# 21_HUB.net
KiCad netlist of a schematic drawn in Altium Designer
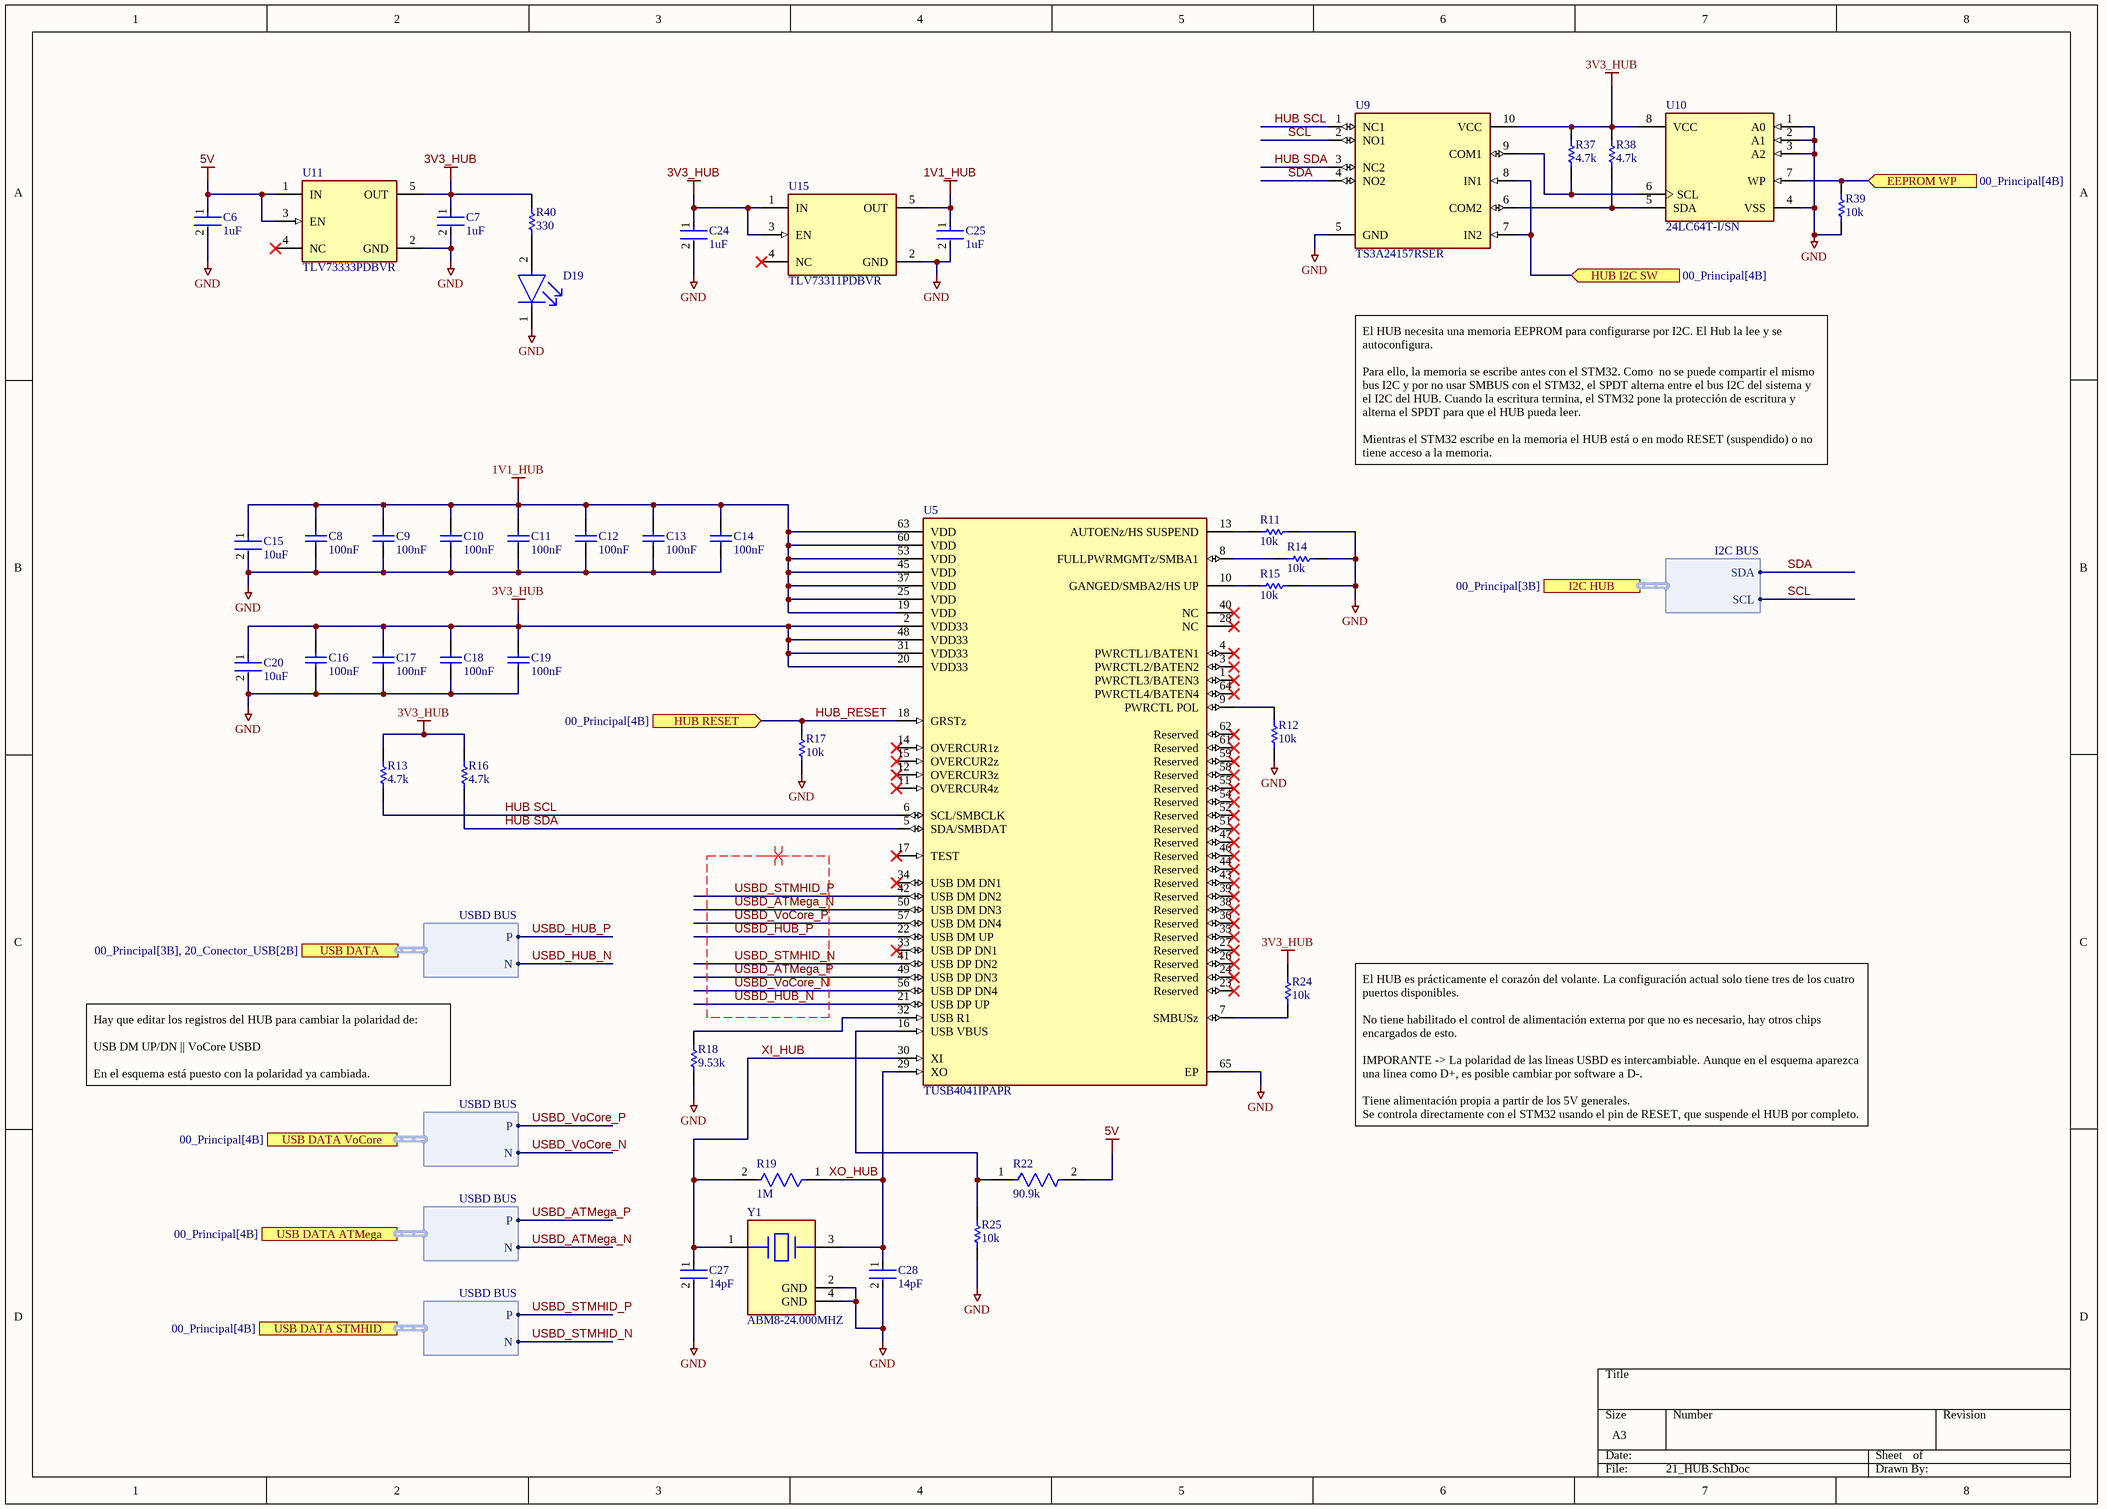
[diagram p0: 21_HUB.SchDoc]

(export (version "E")
  (design (tool "Eeschema 10.0.6"))
  (components
    (comp (ref "C6")
      (value "1uF")
      (footprint "FP-C0402C-BB-IPC_B")
      (description "CAP CER 1UF 16V X5R 0402")
      (fields (field (name "TOLERANCE") "10%"))
      (libsource (lib "Altium Content Vault") (part "b4654b650e69147ec39a6b967a45e02"))
    )
    (comp (ref "C7")
      (value "1uF")
      (footprint "FP-C0402C-BB-IPC_B")
      (description "CAP CER 1UF 16V X5R 0402")
      (fields (field (name "TOLERANCE") "10%"))
      (libsource (lib "Altium Content Vault") (part "b4654b650e69147ec39a6b967a45e02"))
    )
    (comp (ref "C8")
      (value "100nF")
      (footprint "CAPC1005X55X25NL05T05")
      (fields (field (name "MANUFACTURER") "Vitramon") (field (name "PART NUMBER") "VJ0402Y104KXJCW1BC"))
      (libsource (lib "Altium Content Vault") (part "CAP"))
    )
    (comp (ref "C9")
      (value "100nF")
      (footprint "CAPC1005X55X25NL05T05")
      (fields (field (name "MANUFACTURER") "Vitramon") (field (name "PART NUMBER") "VJ0402Y104KXJCW1BC"))
      (libsource (lib "Altium Content Vault") (part "CAP"))
    )
    (comp (ref "C10")
      (value "100nF")
      (footprint "CAPC1005X55X25NL05T05")
      (fields (field (name "MANUFACTURER") "Vitramon") (field (name "PART NUMBER") "VJ0402Y104KXJCW1BC"))
      (libsource (lib "Altium Content Vault") (part "CAP"))
    )
    (comp (ref "C11")
      (value "100nF")
      (footprint "CAPC1005X55X25NL05T05")
      (fields (field (name "MANUFACTURER") "Vitramon") (field (name "PART NUMBER") "VJ0402Y104KXJCW1BC"))
      (libsource (lib "Altium Content Vault") (part "CAP"))
    )
    (comp (ref "C12")
      (value "100nF")
      (footprint "CAPC1005X55X25NL05T05")
      (fields (field (name "MANUFACTURER") "Vitramon") (field (name "PART NUMBER") "VJ0402Y104KXJCW1BC"))
      (libsource (lib "Altium Content Vault") (part "CAP"))
    )
    (comp (ref "C13")
      (value "100nF")
      (footprint "CAPC1005X55X25NL05T05")
      (fields (field (name "MANUFACTURER") "Vitramon") (field (name "PART NUMBER") "VJ0402Y104KXJCW1BC"))
      (libsource (lib "Altium Content Vault") (part "CAP"))
    )
    (comp (ref "C14")
      (value "100nF")
      (footprint "CAPC1005X55X25NL05T05")
      (fields (field (name "MANUFACTURER") "Vitramon") (field (name "PART NUMBER") "VJ0402Y104KXJCW1BC"))
      (libsource (lib "Altium Content Vault") (part "CAP"))
    )
    (comp (ref "C15")
      (value "10uF")
      (footprint "FP-GRM155-0_2-MFG")
      (description "Chip Multilayer Ceramic Capacitors for General Purpose, 0402, 10uF, X5R, 15%, 20%, 4V")
      (libsource (lib "Altium Content Vault") (part "b4654b650e69147ec39a6b967a45e02"))
    )
    (comp (ref "C16")
      (value "100nF")
      (footprint "CAPC1005X55X25NL05T05")
      (fields (field (name "MANUFACTURER") "Vitramon") (field (name "PART NUMBER") "VJ0402Y104KXJCW1BC"))
      (libsource (lib "Altium Content Vault") (part "CAP"))
    )
    (comp (ref "C17")
      (value "100nF")
      (footprint "CAPC1005X55X25NL05T05")
      (fields (field (name "MANUFACTURER") "Vitramon") (field (name "PART NUMBER") "VJ0402Y104KXJCW1BC"))
      (libsource (lib "Altium Content Vault") (part "CAP"))
    )
    (comp (ref "C18")
      (value "100nF")
      (footprint "CAPC1005X55X25NL05T05")
      (fields (field (name "MANUFACTURER") "Vitramon") (field (name "PART NUMBER") "VJ0402Y104KXJCW1BC"))
      (libsource (lib "Altium Content Vault") (part "CAP"))
    )
    (comp (ref "C19")
      (value "100nF")
      (footprint "CAPC1005X55X25NL05T05")
      (fields (field (name "MANUFACTURER") "Vitramon") (field (name "PART NUMBER") "VJ0402Y104KXJCW1BC"))
      (libsource (lib "Altium Content Vault") (part "CAP"))
    )
    (comp (ref "C20")
      (value "10uF")
      (footprint "FP-GRM155-0_2-MFG")
      (description "Chip Multilayer Ceramic Capacitors for General Purpose, 0402, 10uF, X5R, 15%, 20%, 4V")
      (libsource (lib "Altium Content Vault") (part "b4654b650e69147ec39a6b967a45e02"))
    )
    (comp (ref "C24")
      (value "1uF")
      (footprint "FP-C0402C-BB-IPC_B")
      (description "CAP CER 1UF 16V X5R 0402")
      (fields (field (name "TOLERANCE") "10%"))
      (libsource (lib "Altium Content Vault") (part "b4654b650e69147ec39a6b967a45e02"))
    )
    (comp (ref "C25")
      (value "1uF")
      (footprint "FP-C0402C-BB-IPC_B")
      (description "CAP CER 1UF 16V X5R 0402")
      (fields (field (name "TOLERANCE") "10%"))
      (libsource (lib "Altium Content Vault") (part "b4654b650e69147ec39a6b967a45e02"))
    )
    (comp (ref "C27")
      (value "14pF")
      (footprint "FP-GJM155-0_05-IPC_C")
      (description "Multi-Layer Ceramic Capacitor 14pF C0G  ±1% 0402 Paper T/R")
      (libsource (lib "Altium Content Vault") (part "02cd4be3c70576c341d710602a673aa"))
    )
    (comp (ref "C28")
      (value "14pF")
      (footprint "FP-GJM155-0_05-IPC_C")
      (description "Multi-Layer Ceramic Capacitor 14pF C0G  ±1% 0402 Paper T/R")
      (libsource (lib "Altium Content Vault") (part "02cd4be3c70576c341d710602a673aa"))
    )
    (comp (ref "D19")
      (value "APHD1608LZGCK")
      (footprint "FP-APHD1608LZGCK-MFG")
      (description "LED GREEN CLEAR 1608 SMD")
      (libsource (lib "Altium Content Vault") (part "8706943c75ba83719d021d2fdc84c58"))
    )
    (comp (ref "R11")
      (value "10k")
      (footprint "RESC1005X40X25ML05T05")
      (fields (field (name "MANUFACTURER") "Panasonic") (field (name "PART NUMBER") "ERJ-2RHD1002X"))
      (libsource (lib "Altium Content Vault") (part "RES"))
    )
    (comp (ref "R12")
      (value "10k")
      (footprint "RESC1005X40X25NL05T05")
      (fields (field (name "MANUFACTURER") "Panasonic") (field (name "PART NUMBER") "ERJ-2RHD1002X"))
      (libsource (lib "Altium Content Vault") (part "RES"))
    )
    (comp (ref "R13")
      (value "4.7k")
      (footprint "RESC1005X40X25ML05T10")
      (fields (field (name "MANUFACTURER") "Panasonic") (field (name "PART NUMBER") "ERJ-S02F4701X"))
      (libsource (lib "Altium Content Vault") (part "RES"))
    )
    (comp (ref "R14")
      (value "10k")
      (footprint "RESC1005X40X25ML05T05")
      (fields (field (name "MANUFACTURER") "Panasonic") (field (name "PART NUMBER") "ERJ-2RHD1002X"))
      (libsource (lib "Altium Content Vault") (part "RES"))
    )
    (comp (ref "R15")
      (value "10k")
      (footprint "RESC1005X40X25ML05T05")
      (fields (field (name "MANUFACTURER") "Panasonic") (field (name "PART NUMBER") "ERJ-2RHD1002X"))
      (libsource (lib "Altium Content Vault") (part "RES"))
    )
    (comp (ref "R16")
      (value "4.7k")
      (footprint "RESC1005X40X25ML05T10")
      (fields (field (name "MANUFACTURER") "Panasonic") (field (name "PART NUMBER") "ERJ-S02F4701X"))
      (libsource (lib "Altium Content Vault") (part "RES"))
    )
    (comp (ref "R17")
      (value "10k")
      (footprint "RESC1005X40X25ML05T05")
      (fields (field (name "MANUFACTURER") "Panasonic") (field (name "PART NUMBER") "ERJ-2RHD1002X"))
      (libsource (lib "Altium Content Vault") (part "RES"))
    )
    (comp (ref "R18")
      (value "9.53k")
      (footprint "RESC1609X50X30NL10T20")
      (fields (field (name "MANUFACTURER") "Vishay Dale") (field (name "PART NUMBER") "CRCW06039K53FKEA"))
      (libsource (lib "Altium Content Vault") (part "RES"))
    )
    (comp (ref "R19")
      (value "1M")
      (footprint "FP-CRCW0402-C-e3-IPC_B")
      (description "RES 1M OHM 1% 1/16W 0402")
      (fields (field (name "TOLERANCE") "1%"))
      (libsource (lib "Altium Content Vault") (part "1029c3af85768c4190bb7ad29bc67b5"))
    )
    (comp (ref "R22")
      (value "90.9k")
      (footprint "FP-RK73H1E-IPC_C")
      (description "90.9kΩ ±1% 0.1W Chip Resistor 0402 Flat Chip (Anti-Sulfuration) AEC-Q200 Qualified")
      (fields (field (name "TOLERANCE") "1%"))
      (libsource (lib "Altium Content Vault") (part "1029c3af85768c4190bb7ad29bc67b5"))
    )
    (comp (ref "R24")
      (value "10k")
      (footprint "RESC1005X40X25NL05T05")
      (fields (field (name "MANUFACTURER") "Panasonic") (field (name "PART NUMBER") "ERJ-2RHD1002X"))
      (libsource (lib "Altium Content Vault") (part "RES"))
    )
    (comp (ref "R25")
      (value "10k")
      (footprint "RESC1005X40X25NL05T05")
      (fields (field (name "MANUFACTURER") "Panasonic") (field (name "PART NUMBER") "ERJ-2RHD1002X"))
      (libsource (lib "Altium Content Vault") (part "RES"))
    )
    (comp (ref "R37")
      (value "4.7k")
      (footprint "RESC1005X40X25ML05T10")
      (fields (field (name "MANUFACTURER") "Panasonic") (field (name "PART NUMBER") "ERJ-S02F4701X"))
      (libsource (lib "Altium Content Vault") (part "RES"))
    )
    (comp (ref "R38")
      (value "4.7k")
      (footprint "RESC1005X40X25ML05T10")
      (fields (field (name "MANUFACTURER") "Panasonic") (field (name "PART NUMBER") "ERJ-S02F4701X"))
      (libsource (lib "Altium Content Vault") (part "RES"))
    )
    (comp (ref "R39")
      (value "10k")
      (footprint "RESC1005X40X25ML05T05")
      (fields (field (name "MANUFACTURER") "Panasonic") (field (name "PART NUMBER") "ERJ-2RHD1002X"))
      (libsource (lib "Altium Content Vault") (part "RES"))
    )
    (comp (ref "R40")
      (value "330")
      (footprint "RESC1005X40X25NL10T10")
      (fields (field (name "MANUFACTURER") "Panasonic") (field (name "PART NUMBER") "ERA2AEB331X"))
      (libsource (lib "Altium Content Vault") (part "RES"))
    )
    (comp (ref "U5")
      (value "TUSB4041IPAPR")
      (footprint "FP-PAP0064K-MFG")
      (description "IC USB 2.0 4PORT HUB 64HTQFP")
      (fields
        (field (name "MANUFACTURER") "Texas Instruments")
        (field (name "OCTOPART") "https://octopart.com/tusb4041ipapr-texas+instruments-61734371")
      )
      (libsource (lib "Altium Content Vault") (part "5e978d452e673cf9c6e58b86f9ac1bd"))
    )
    (comp (ref "U9")
      (value "TS3A24157RSER")
      (footprint "FP-RSE0010A-MFG")
      (description "IC SWITCH DUAL SPDT 10UQFN")
      (libsource (lib "Altium Content Vault") (part "1cf126cdf601fc2f4e01c6c6da6e1d2"))
    )
    (comp (ref "U10")
      (value "24LC64T-I/SN")
      (footprint "FP-C04-057-SN-MFG")
      (description "IC EEPROM 64K I2C 400KHZ 8SOIC")
      (fields
        (field (name "OCTOPART") "https://octopart.com/24lc64t-i%2Fsn-microchip-451854")
        (field (name "MANUFACTURER") "Microchip Technology")
      )
      (libsource (lib "Altium Content Vault") (part "aa9a952ee66a023cd78eade27961581"))
    )
    (comp (ref "U11")
      (value "TLV73333PDBVR")
      (footprint "FP-DBV0005A-MFG")
      (description "IC REG LINEAR 3.3V 300MA SOT23-5")
      (fields
        (field (name "MANUFACTURER") "Texas Instruments")
        (field (name "OCTOPART") "https://octopart.com/tlv73333pdbvr-texas+instruments-51080890")
      )
      (libsource (lib "Altium Content Vault") (part "10cdd6a861ce8db355dac0efc8b397e"))
    )
    (comp (ref "U15")
      (value "TLV73311PDBVR")
      (footprint "FP-DBV0005A-IPC_C")
      (description "IC REG LINEAR 1.1V 300MA SOT23-5")
      (libsource (lib "Altium Content Vault") (part "66ca6db733a9cb813c480efc7723418"))
    )
    (comp (ref "Y1")
      (value "ABM8-24.000MHZ")
      (footprint "FP-ABM8-MFG")
      (description "Crystal 24MHz ±10ppm 12pF SMD-4 3.2mm x 2.5mm")
      (libsource (lib "Altium Content Vault") (part "dfdb7f9a12507849fb681da9a70121c"))
    )
  )
  (nets
    (net (code "4") (name "/EEPROM WP") (class "Default")
      (node (ref "R39") (pin "1") (pinfunction "1_1") (pintype "passive"))
      (node (ref "U10") (pin "7") (pinfunction "WP_7") (pintype "input"))
    )
    (net (code "5") (name "/HUB I2C SW") (class "Default")
      (node (ref "U9") (pin "7") (pinfunction "IN2_7") (pintype "input"))
      (node (ref "U9") (pin "8") (pinfunction "IN1_8") (pintype "input"))
    )
    (net (code "6") (name "/HUB SCL") (class "Default")
      (node (ref "R13") (pin "1") (pinfunction "1_1") (pintype "passive"))
      (node (ref "U5") (pin "6") (pinfunction "SCL/SMBCLK_6") (pintype "bidirectional"))
      (node (ref "U9") (pin "1") (pinfunction "NC1_1") (pintype "bidirectional"))
    )
    (net (code "7") (name "/HUB SDA") (class "Default")
      (node (ref "R16") (pin "1") (pinfunction "1_1") (pintype "passive"))
      (node (ref "U5") (pin "5") (pinfunction "SDA/SMBDAT_5") (pintype "bidirectional"))
      (node (ref "U9") (pin "3") (pinfunction "NC2_3") (pintype "bidirectional"))
    )
    (net (code "8") (name "/HUB_RESET") (class "Default")
      (node (ref "R17") (pin "1") (pinfunction "1_1") (pintype "passive"))
      (node (ref "U5") (pin "18") (pinfunction "GRSTz_18") (pintype "input"))
    )
    (net (code "9") (name "/SCL") (class "Default")
      (node (ref "U9") (pin "2") (pinfunction "NO1_2") (pintype "bidirectional"))
    )
    (net (code "10") (name "/SDA") (class "Default")
      (node (ref "U9") (pin "4") (pinfunction "NO2_4") (pintype "bidirectional"))
    )
    (net (code "11") (name "/USBD_ATMega_N") (class "Default")
      (node (ref "U5") (pin "50") (pinfunction "USB_DM_DN3_50") (pintype "bidirectional"))
    )
    (net (code "12") (name "/USBD_ATMega_P") (class "Default")
      (node (ref "U5") (pin "49") (pinfunction "USB_DP_DN3_49") (pintype "bidirectional"))
    )
    (net (code "13") (name "/USBD_HUB_N") (class "Default")
      (node (ref "U5") (pin "21") (pinfunction "USB_DP_UP_21") (pintype "bidirectional"))
    )
    (net (code "14") (name "/USBD_HUB_P") (class "Default")
      (node (ref "U5") (pin "22") (pinfunction "USB_DM_UP_22") (pintype "bidirectional"))
    )
    (net (code "15") (name "/USBD_STMHID_N") (class "Default")
      (node (ref "U5") (pin "41") (pinfunction "USB_DP_DN2_41") (pintype "bidirectional"))
    )
    (net (code "16") (name "/USBD_STMHID_P") (class "Default")
      (node (ref "U5") (pin "42") (pinfunction "USB_DM_DN2_42") (pintype "bidirectional"))
    )
    (net (code "17") (name "/USBD_VoCore_N") (class "Default")
      (node (ref "U5") (pin "56") (pinfunction "USB_DP_DN4_56") (pintype "bidirectional"))
    )
    (net (code "18") (name "/USBD_VoCore_P") (class "Default")
      (node (ref "U5") (pin "57") (pinfunction "USB_DM_DN4_57") (pintype "bidirectional"))
    )
    (net (code "19") (name "/XI_HUB") (class "Default")
      (node (ref "C27") (pin "1") (pinfunction "1_1") (pintype "passive"))
      (node (ref "R19") (pin "2") (pinfunction "2_2") (pintype "passive"))
      (node (ref "U5") (pin "30") (pinfunction "XI_30") (pintype "input"))
      (node (ref "Y1") (pin "1") (pinfunction "1_1") (pintype "passive"))
    )
    (net (code "20") (name "/XO_HUB") (class "Default")
      (node (ref "C28") (pin "1") (pinfunction "1_1") (pintype "passive"))
      (node (ref "R19") (pin "1") (pinfunction "1_1") (pintype "passive"))
      (node (ref "U5") (pin "29") (pinfunction "XO_29") (pintype "input"))
      (node (ref "Y1") (pin "3") (pinfunction "3_3") (pintype "passive"))
    )
    (net (code "23") (name "1V1_HUB") (class "Default")
      (node (ref "C10") (pin "2") (pinfunction "2_2") (pintype "passive"))
      (node (ref "C11") (pin "2") (pinfunction "2_2") (pintype "passive"))
      (node (ref "C12") (pin "2") (pinfunction "2_2") (pintype "passive"))
      (node (ref "C13") (pin "2") (pinfunction "2_2") (pintype "passive"))
      (node (ref "C14") (pin "2") (pinfunction "2_2") (pintype "passive"))
      (node (ref "C15") (pin "1") (pinfunction "1_1") (pintype "passive"))
      (node (ref "C25") (pin "1") (pinfunction "1_1") (pintype "passive"))
      (node (ref "C8") (pin "2") (pinfunction "2_2") (pintype "passive"))
      (node (ref "C9") (pin "2") (pinfunction "2_2") (pintype "passive"))
      (node (ref "U15") (pin "5") (pinfunction "OUT_5") (pintype "power_in"))
      (node (ref "U5") (pin "19") (pinfunction "VDD_19") (pintype "power_in"))
      (node (ref "U5") (pin "25") (pinfunction "VDD_25") (pintype "power_in"))
      (node (ref "U5") (pin "37") (pinfunction "VDD_37") (pintype "power_in"))
      (node (ref "U5") (pin "45") (pinfunction "VDD_45") (pintype "power_in"))
      (node (ref "U5") (pin "53") (pinfunction "VDD_53") (pintype "power_in"))
      (node (ref "U5") (pin "60") (pinfunction "VDD_60") (pintype "power_in"))
      (node (ref "U5") (pin "63") (pinfunction "VDD_63") (pintype "power_in"))
    )
    (net (code "24") (name "3V3_HUB") (class "Default")
      (node (ref "C16") (pin "2") (pinfunction "2_2") (pintype "passive"))
      (node (ref "C17") (pin "2") (pinfunction "2_2") (pintype "passive"))
      (node (ref "C18") (pin "2") (pinfunction "2_2") (pintype "passive"))
      (node (ref "C19") (pin "2") (pinfunction "2_2") (pintype "passive"))
      (node (ref "C20") (pin "1") (pinfunction "1_1") (pintype "passive"))
      (node (ref "C24") (pin "1") (pinfunction "1_1") (pintype "passive"))
      (node (ref "C7") (pin "1") (pinfunction "1_1") (pintype "passive"))
      (node (ref "R13") (pin "2") (pinfunction "2_2") (pintype "passive"))
      (node (ref "R16") (pin "2") (pinfunction "2_2") (pintype "passive"))
      (node (ref "R24") (pin "2") (pinfunction "2_2") (pintype "passive"))
      (node (ref "R37") (pin "2") (pinfunction "2_2") (pintype "passive"))
      (node (ref "R38") (pin "2") (pinfunction "2_2") (pintype "passive"))
      (node (ref "R40") (pin "2") (pinfunction "2_2") (pintype "passive"))
      (node (ref "U10") (pin "8") (pinfunction "VCC_8") (pintype "power_in"))
      (node (ref "U11") (pin "5") (pinfunction "OUT_5") (pintype "power_in"))
      (node (ref "U15") (pin "1") (pinfunction "IN_1") (pintype "power_in"))
      (node (ref "U15") (pin "3") (pinfunction "EN_3") (pintype "input"))
      (node (ref "U5") (pin "2") (pinfunction "VDD33_2") (pintype "power_in"))
      (node (ref "U5") (pin "20") (pinfunction "VDD33_20") (pintype "power_in"))
      (node (ref "U5") (pin "31") (pinfunction "VDD33_31") (pintype "power_in"))
      (node (ref "U5") (pin "48") (pinfunction "VDD33_48") (pintype "power_in"))
      (node (ref "U9") (pin "10") (pinfunction "VCC_10") (pintype "power_in"))
    )
    (net (code "25") (name "5V") (class "Default")
      (node (ref "C6") (pin "1") (pinfunction "1_1") (pintype "passive"))
      (node (ref "R22") (pin "2") (pinfunction "2_2") (pintype "passive"))
      (node (ref "U11") (pin "1") (pinfunction "IN_1") (pintype "passive"))
      (node (ref "U11") (pin "3") (pinfunction "EN_3") (pintype "input"))
    )
    (net (code "26") (name "GND") (class "Default")
      (node (ref "C10") (pin "1") (pinfunction "1_1") (pintype "passive"))
      (node (ref "C11") (pin "1") (pinfunction "1_1") (pintype "passive"))
      (node (ref "C12") (pin "1") (pinfunction "1_1") (pintype "passive"))
      (node (ref "C13") (pin "1") (pinfunction "1_1") (pintype "passive"))
      (node (ref "C14") (pin "1") (pinfunction "1_1") (pintype "passive"))
      (node (ref "C15") (pin "2") (pinfunction "2_2") (pintype "passive"))
      (node (ref "C16") (pin "1") (pinfunction "1_1") (pintype "passive"))
      (node (ref "C17") (pin "1") (pinfunction "1_1") (pintype "passive"))
      (node (ref "C18") (pin "1") (pinfunction "1_1") (pintype "passive"))
      (node (ref "C19") (pin "1") (pinfunction "1_1") (pintype "passive"))
      (node (ref "C20") (pin "2") (pinfunction "2_2") (pintype "passive"))
      (node (ref "C24") (pin "2") (pinfunction "2_2") (pintype "passive"))
      (node (ref "C25") (pin "2") (pinfunction "2_2") (pintype "passive"))
      (node (ref "C27") (pin "2") (pinfunction "2_2") (pintype "passive"))
      (node (ref "C28") (pin "2") (pinfunction "2_2") (pintype "passive"))
      (node (ref "C6") (pin "2") (pinfunction "2_2") (pintype "passive"))
      (node (ref "C7") (pin "2") (pinfunction "2_2") (pintype "passive"))
      (node (ref "C8") (pin "1") (pinfunction "1_1") (pintype "passive"))
      (node (ref "C9") (pin "1") (pinfunction "1_1") (pintype "passive"))
      (node (ref "D19") (pin "1") (pinfunction "C_1") (pintype "passive"))
      (node (ref "R11") (pin "1") (pinfunction "1_1") (pintype "passive"))
      (node (ref "R12") (pin "1") (pinfunction "1_1") (pintype "passive"))
      (node (ref "R14") (pin "1") (pinfunction "1_1") (pintype "passive"))
      (node (ref "R15") (pin "1") (pinfunction "1_1") (pintype "passive"))
      (node (ref "R17") (pin "2") (pinfunction "2_2") (pintype "passive"))
      (node (ref "R18") (pin "1") (pinfunction "1_1") (pintype "passive"))
      (node (ref "R25") (pin "1") (pinfunction "1_1") (pintype "passive"))
      (node (ref "R39") (pin "2") (pinfunction "2_2") (pintype "passive"))
      (node (ref "U10") (pin "1") (pinfunction "A0_1") (pintype "input"))
      (node (ref "U10") (pin "2") (pinfunction "A1_2") (pintype "input"))
      (node (ref "U10") (pin "3") (pinfunction "A2_3") (pintype "input"))
      (node (ref "U10") (pin "4") (pinfunction "VSS_4") (pintype "power_in"))
      (node (ref "U11") (pin "2") (pinfunction "GND_2") (pintype "passive"))
      (node (ref "U15") (pin "2") (pinfunction "GND_2") (pintype "passive"))
      (node (ref "U5") (pin "65") (pinfunction "EP_65") (pintype "passive"))
      (node (ref "U9") (pin "5") (pinfunction "GND_5") (pintype "power_in"))
      (node (ref "Y1") (pin "2") (pinfunction "GND_2") (pintype "power_in"))
      (node (ref "Y1") (pin "4") (pinfunction "GND_4") (pintype "power_in"))
    )
    (net (code "27") (name "Net-(D19-A)") (class "Default")
      (node (ref "D19") (pin "2") (pinfunction "A_2") (pintype "passive"))
      (node (ref "R40") (pin "1") (pinfunction "1_1") (pintype "passive"))
    )
    (net (code "28") (name "Net-(U5-AUTOENz{slash}HS_SUSPEND)") (class "Default")
      (node (ref "R11") (pin "2") (pinfunction "2_2") (pintype "passive"))
      (node (ref "U5") (pin "13") (pinfunction "AUTOENz/HS_SUSPEND_13") (pintype "passive"))
    )
    (net (code "29") (name "Net-(U5-FULLPWRMGMTz{slash}SMBA1)") (class "Default")
      (node (ref "R14") (pin "2") (pinfunction "2_2") (pintype "passive"))
      (node (ref "U5") (pin "8") (pinfunction "FULLPWRMGMTz/SMBA1_8") (pintype "bidirectional"))
    )
    (net (code "30") (name "Net-(U5-GANGED{slash}SMBA2{slash}HS_UP)") (class "Default")
      (node (ref "R15") (pin "2") (pinfunction "2_2") (pintype "passive"))
      (node (ref "U5") (pin "10") (pinfunction "GANGED/SMBA2/HS_UP_10") (pintype "passive"))
    )
    (net (code "31") (name "Net-(U5-PWRCTL_POL)") (class "Default")
      (node (ref "R12") (pin "2") (pinfunction "2_2") (pintype "passive"))
      (node (ref "U5") (pin "9") (pinfunction "PWRCTL_POL_9") (pintype "bidirectional"))
    )
    (net (code "32") (name "Net-(U5-SMBUSz)") (class "Default")
      (node (ref "R24") (pin "1") (pinfunction "1_1") (pintype "passive"))
      (node (ref "U5") (pin "7") (pinfunction "SMBUSz_7") (pintype "bidirectional"))
    )
    (net (code "33") (name "Net-(U5-USB_R1)") (class "Default")
      (node (ref "R18") (pin "2") (pinfunction "2_2") (pintype "passive"))
      (node (ref "U5") (pin "32") (pinfunction "USB_R1_32") (pintype "input"))
    )
    (net (code "34") (name "Net-(U5-USB_VBUS)") (class "Default")
      (node (ref "R22") (pin "1") (pinfunction "1_1") (pintype "passive"))
      (node (ref "R25") (pin "2") (pinfunction "2_2") (pintype "passive"))
      (node (ref "U5") (pin "16") (pinfunction "USB_VBUS_16") (pintype "input"))
    )
    (net (code "35") (name "Net-(U10-SCL)") (class "Default")
      (node (ref "R37") (pin "1") (pinfunction "1_1") (pintype "passive"))
      (node (ref "U10") (pin "6") (pinfunction "SCL_6") (pintype "open_collector"))
      (node (ref "U9") (pin "9") (pinfunction "COM1_9") (pintype "bidirectional"))
    )
    (net (code "36") (name "Net-(U10-SDA)") (class "Default")
      (node (ref "R38") (pin "1") (pinfunction "1_1") (pintype "passive"))
      (node (ref "U10") (pin "5") (pinfunction "SDA_5") (pintype "open_collector"))
      (node (ref "U9") (pin "6") (pinfunction "COM2_6") (pintype "bidirectional"))
    )
    (net (code "37") (name "unconnected-(U5-NC-Pad28)") (class "Default")
      (node (ref "U5") (pin "28") (pinfunction "NC_28") (pintype "passive+no_connect"))
    )
    (net (code "38") (name "unconnected-(U5-NC-Pad40)") (class "Default")
      (node (ref "U5") (pin "40") (pinfunction "NC_40") (pintype "passive+no_connect"))
    )
    (net (code "39") (name "unconnected-(U5-OVERCUR1z-Pad14)") (class "Default")
      (node (ref "U5") (pin "14") (pinfunction "OVERCUR1z_14") (pintype "input+no_connect"))
    )
    (net (code "40") (name "unconnected-(U5-OVERCUR2z-Pad15)") (class "Default")
      (node (ref "U5") (pin "15") (pinfunction "OVERCUR2z_15") (pintype "input+no_connect"))
    )
    (net (code "41") (name "unconnected-(U5-OVERCUR3z-Pad12)") (class "Default")
      (node (ref "U5") (pin "12") (pinfunction "OVERCUR3z_12") (pintype "input+no_connect"))
    )
    (net (code "42") (name "unconnected-(U5-OVERCUR4z-Pad11)") (class "Default")
      (node (ref "U5") (pin "11") (pinfunction "OVERCUR4z_11") (pintype "input+no_connect"))
    )
    (net (code "43") (name "unconnected-(U5-PWRCTL1{slash}BATEN1-Pad4)") (class "Default")
      (node (ref "U5") (pin "4") (pinfunction "PWRCTL1/BATEN1_4") (pintype "bidirectional+no_connect"))
    )
    (net (code "44") (name "unconnected-(U5-PWRCTL2{slash}BATEN2-Pad3)") (class "Default")
      (node (ref "U5") (pin "3") (pinfunction "PWRCTL2/BATEN2_3") (pintype "bidirectional+no_connect"))
    )
    (net (code "45") (name "unconnected-(U5-PWRCTL3{slash}BATEN3-Pad1)") (class "Default")
      (node (ref "U5") (pin "1") (pinfunction "PWRCTL3/BATEN3_1") (pintype "bidirectional+no_connect"))
    )
    (net (code "46") (name "unconnected-(U5-PWRCTL4{slash}BATEN4-Pad64)") (class "Default")
      (node (ref "U5") (pin "64") (pinfunction "PWRCTL4/BATEN4_64") (pintype "bidirectional+no_connect"))
    )
    (net (code "47") (name "unconnected-(U5-Reserved-Pad23)") (class "Default")
      (node (ref "U5") (pin "23") (pinfunction "Reserved_23") (pintype "bidirectional+no_connect"))
    )
    (net (code "48") (name "unconnected-(U5-Reserved-Pad24)") (class "Default")
      (node (ref "U5") (pin "24") (pinfunction "Reserved_24") (pintype "bidirectional+no_connect"))
    )
    (net (code "49") (name "unconnected-(U5-Reserved-Pad26)") (class "Default")
      (node (ref "U5") (pin "26") (pinfunction "Reserved_26") (pintype "bidirectional+no_connect"))
    )
    (net (code "50") (name "unconnected-(U5-Reserved-Pad27)") (class "Default")
      (node (ref "U5") (pin "27") (pinfunction "Reserved_27") (pintype "bidirectional+no_connect"))
    )
    (net (code "51") (name "unconnected-(U5-Reserved-Pad35)") (class "Default")
      (node (ref "U5") (pin "35") (pinfunction "Reserved_35") (pintype "bidirectional+no_connect"))
    )
    (net (code "52") (name "unconnected-(U5-Reserved-Pad36)") (class "Default")
      (node (ref "U5") (pin "36") (pinfunction "Reserved_36") (pintype "bidirectional+no_connect"))
    )
    (net (code "53") (name "unconnected-(U5-Reserved-Pad38)") (class "Default")
      (node (ref "U5") (pin "38") (pinfunction "Reserved_38") (pintype "bidirectional+no_connect"))
    )
    (net (code "54") (name "unconnected-(U5-Reserved-Pad39)") (class "Default")
      (node (ref "U5") (pin "39") (pinfunction "Reserved_39") (pintype "bidirectional+no_connect"))
    )
    (net (code "55") (name "unconnected-(U5-Reserved-Pad43)") (class "Default")
      (node (ref "U5") (pin "43") (pinfunction "Reserved_43") (pintype "bidirectional+no_connect"))
    )
    (net (code "56") (name "unconnected-(U5-Reserved-Pad44)") (class "Default")
      (node (ref "U5") (pin "44") (pinfunction "Reserved_44") (pintype "bidirectional+no_connect"))
    )
    (net (code "57") (name "unconnected-(U5-Reserved-Pad46)") (class "Default")
      (node (ref "U5") (pin "46") (pinfunction "Reserved_46") (pintype "bidirectional+no_connect"))
    )
    (net (code "58") (name "unconnected-(U5-Reserved-Pad47)") (class "Default")
      (node (ref "U5") (pin "47") (pinfunction "Reserved_47") (pintype "bidirectional+no_connect"))
    )
    (net (code "59") (name "unconnected-(U5-Reserved-Pad51)") (class "Default")
      (node (ref "U5") (pin "51") (pinfunction "Reserved_51") (pintype "bidirectional+no_connect"))
    )
    (net (code "60") (name "unconnected-(U5-Reserved-Pad52)") (class "Default")
      (node (ref "U5") (pin "52") (pinfunction "Reserved_52") (pintype "bidirectional+no_connect"))
    )
    (net (code "61") (name "unconnected-(U5-Reserved-Pad54)") (class "Default")
      (node (ref "U5") (pin "54") (pinfunction "Reserved_54") (pintype "bidirectional+no_connect"))
    )
    (net (code "62") (name "unconnected-(U5-Reserved-Pad55)") (class "Default")
      (node (ref "U5") (pin "55") (pinfunction "Reserved_55") (pintype "bidirectional+no_connect"))
    )
    (net (code "63") (name "unconnected-(U5-Reserved-Pad58)") (class "Default")
      (node (ref "U5") (pin "58") (pinfunction "Reserved_58") (pintype "bidirectional+no_connect"))
    )
    (net (code "64") (name "unconnected-(U5-Reserved-Pad59)") (class "Default")
      (node (ref "U5") (pin "59") (pinfunction "Reserved_59") (pintype "bidirectional+no_connect"))
    )
    (net (code "65") (name "unconnected-(U5-Reserved-Pad61)") (class "Default")
      (node (ref "U5") (pin "61") (pinfunction "Reserved_61") (pintype "bidirectional+no_connect"))
    )
    (net (code "66") (name "unconnected-(U5-Reserved-Pad62)") (class "Default")
      (node (ref "U5") (pin "62") (pinfunction "Reserved_62") (pintype "bidirectional+no_connect"))
    )
    (net (code "67") (name "unconnected-(U5-TEST-Pad17)") (class "Default")
      (node (ref "U5") (pin "17") (pinfunction "TEST_17") (pintype "input+no_connect"))
    )
    (net (code "68") (name "unconnected-(U5-USB_DM_DN1-Pad34)") (class "Default")
      (node (ref "U5") (pin "34") (pinfunction "USB_DM_DN1_34") (pintype "bidirectional+no_connect"))
    )
    (net (code "69") (name "unconnected-(U5-USB_DP_DN1-Pad33)") (class "Default")
      (node (ref "U5") (pin "33") (pinfunction "USB_DP_DN1_33") (pintype "bidirectional+no_connect"))
    )
    (net (code "70") (name "unconnected-(U11-NC-Pad4)") (class "Default")
      (node (ref "U11") (pin "4") (pinfunction "NC_4") (pintype "passive+no_connect"))
    )
    (net (code "71") (name "unconnected-(U15-NC-Pad4)") (class "Default")
      (node (ref "U15") (pin "4") (pinfunction "NC_4") (pintype "passive+no_connect"))
    )
  )
)
